# VIDEO.net
KiCad netlist of a schematic drawn in Altium Designer
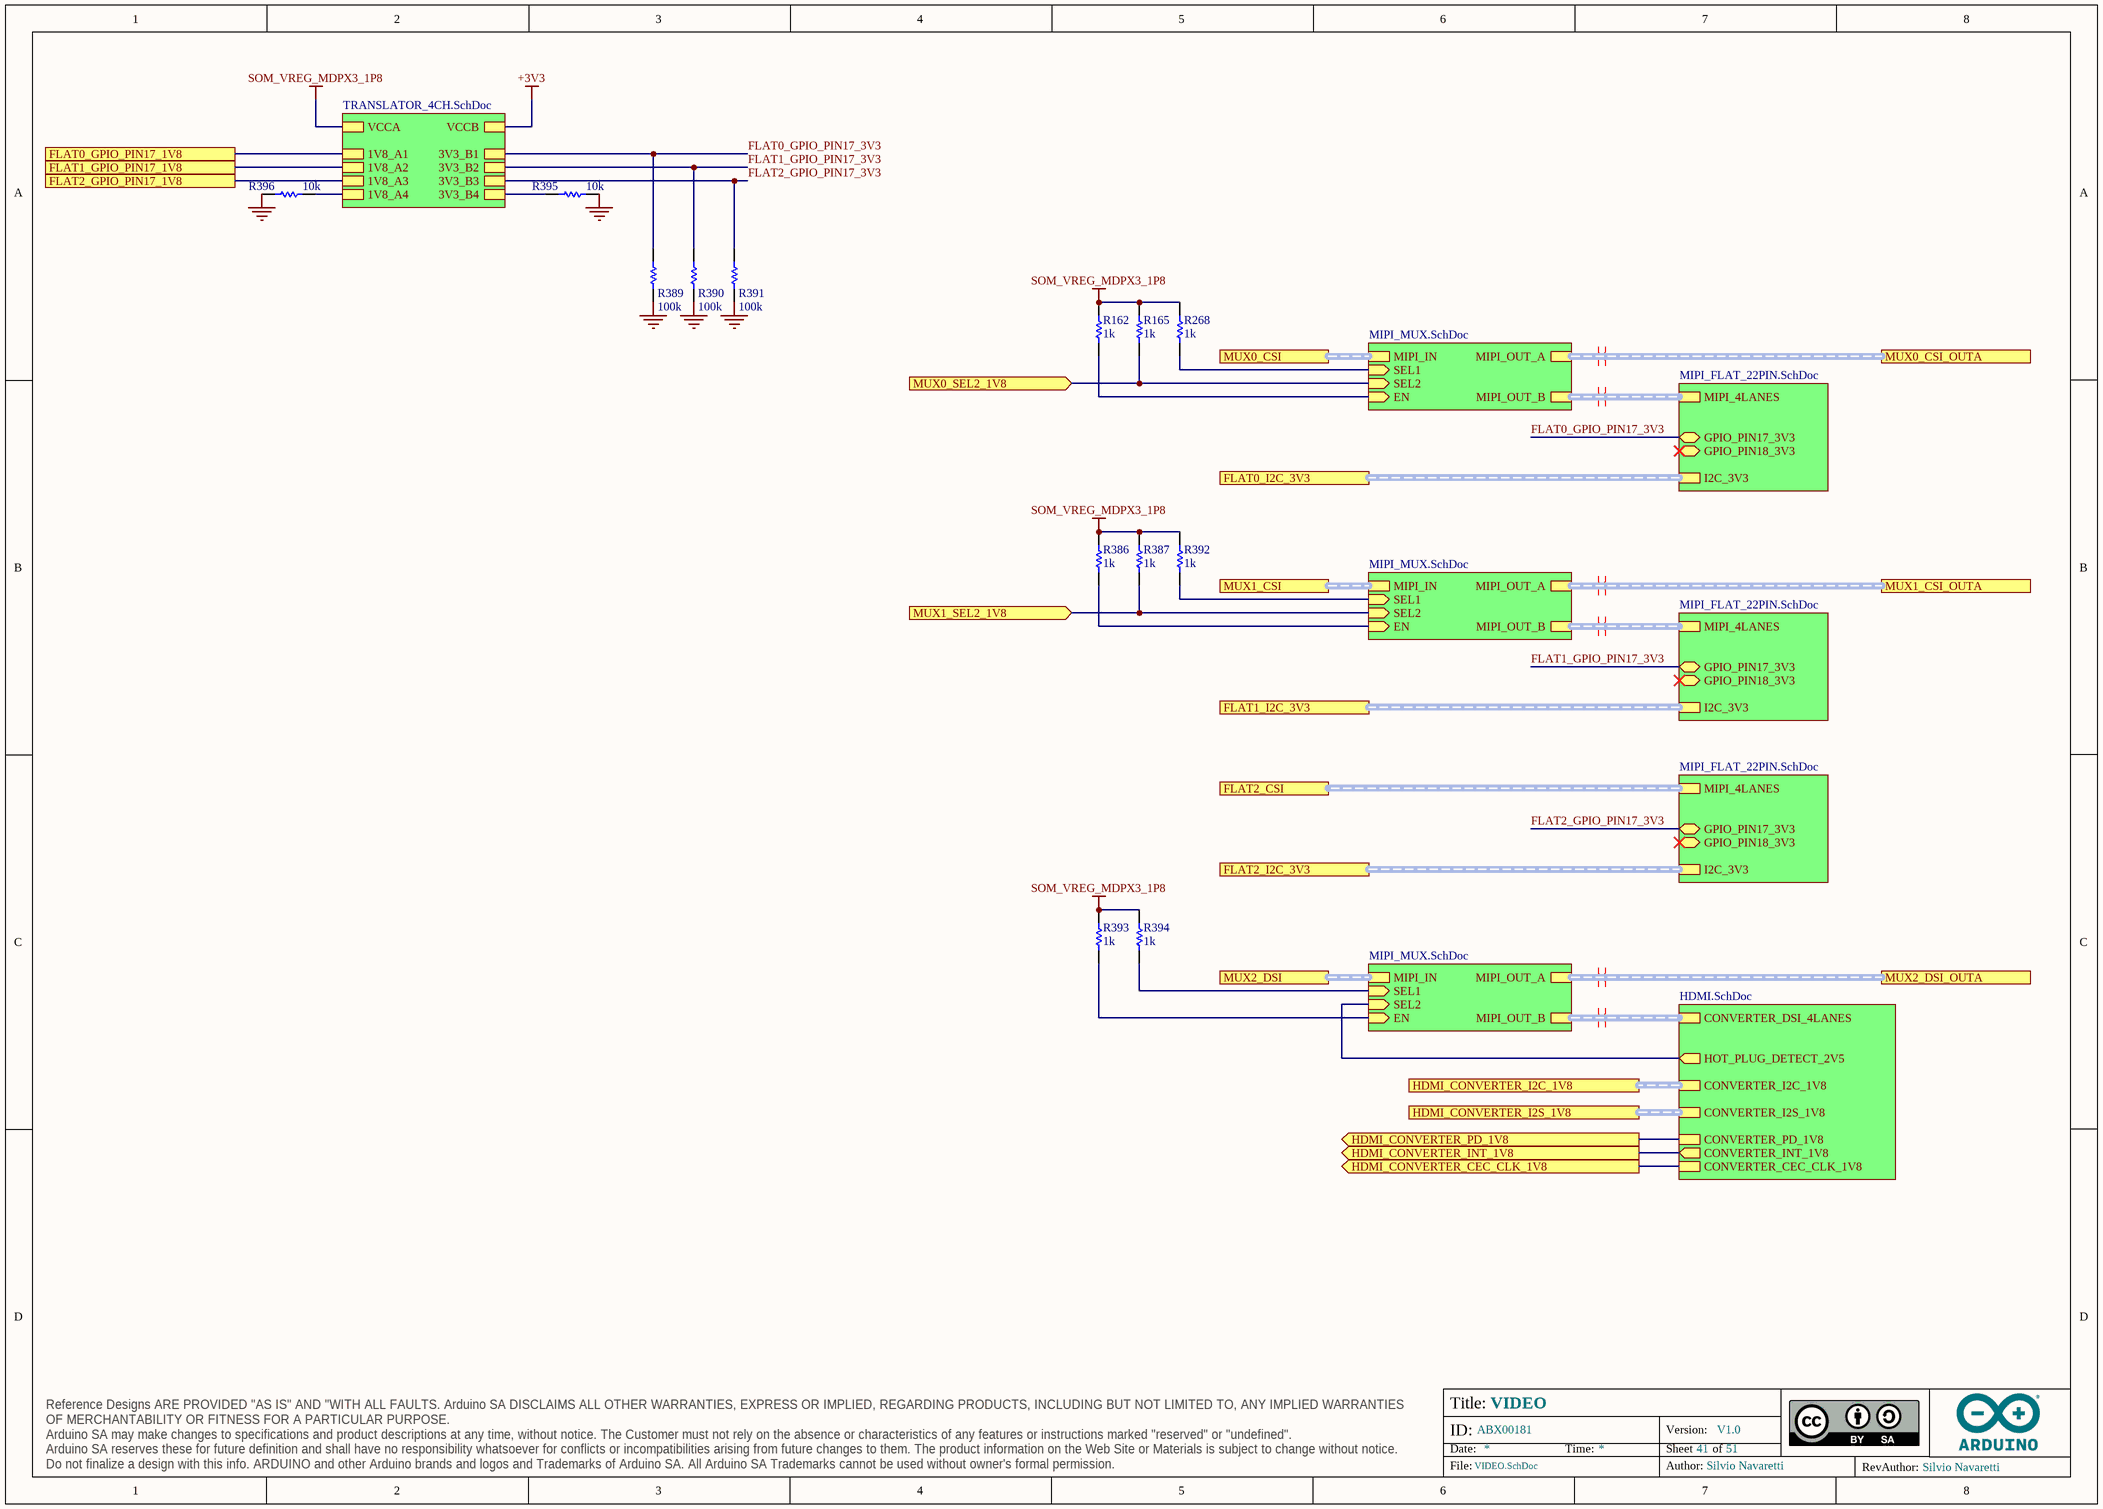
[diagram p0: VIDEO.SchDoc]

(export (version "E")
  (design (tool "Eeschema 10.0.6"))
  (components
    (comp (ref "R162")
      (value "1k")
      (footprint "RES-0201")
      (description "RES CHIP 0201 1k 1% 1/20W")
      (fields (field (name "POWER") "50mW") (field (name "TOLERANCE") "1%"))
      (libsource (lib "Clean") (part "RES"))
    )
    (comp (ref "R165")
      (value "1k")
      (footprint "RES-0201")
      (description "RES CHIP 0201 1k 1% 1/20W")
      (fields (field (name "POWER") "50mW") (field (name "TOLERANCE") "1%"))
      (libsource (lib "Clean") (part "RES"))
    )
    (comp (ref "R268")
      (value "1k")
      (footprint "RES-0201")
      (description "RES CHIP 0201 1k 1% 1/20W")
      (fields (field (name "POWER") "50mW") (field (name "TOLERANCE") "1%"))
      (libsource (lib "Clean") (part "RES"))
    )
    (comp (ref "R386")
      (value "1k")
      (footprint "RES-0201")
      (description "RES CHIP 0201 1k 1% 1/20W")
      (fields (field (name "POWER") "50mW") (field (name "TOLERANCE") "1%"))
      (libsource (lib "Clean") (part "RES"))
    )
    (comp (ref "R387")
      (value "1k")
      (footprint "RES-0201")
      (description "RES CHIP 0201 1k 1% 1/20W")
      (fields (field (name "POWER") "50mW") (field (name "TOLERANCE") "1%"))
      (libsource (lib "Clean") (part "RES"))
    )
    (comp (ref "R389")
      (value "100k")
      (footprint "RES-0201")
      (description "RES CHIP 0201 100k 1% 1/20W")
      (fields (field (name "POWER") "50mW") (field (name "TOLERANCE") "1%"))
      (libsource (lib "Clean") (part "RES"))
    )
    (comp (ref "R390")
      (value "100k")
      (footprint "RES-0201")
      (description "RES CHIP 0201 100k 1% 1/20W")
      (fields (field (name "POWER") "50mW") (field (name "TOLERANCE") "1%"))
      (libsource (lib "Clean") (part "RES"))
    )
    (comp (ref "R391")
      (value "100k")
      (footprint "RES-0201")
      (description "RES CHIP 0201 100k 1% 1/20W")
      (fields (field (name "POWER") "50mW") (field (name "TOLERANCE") "1%"))
      (libsource (lib "Clean") (part "RES"))
    )
    (comp (ref "R392")
      (value "1k")
      (footprint "RES-0201")
      (description "RES CHIP 0201 1k 1% 1/20W")
      (fields (field (name "POWER") "50mW") (field (name "TOLERANCE") "1%"))
      (libsource (lib "Clean") (part "RES"))
    )
    (comp (ref "R393")
      (value "1k")
      (footprint "RES-0201")
      (description "RES CHIP 0201 1k 1% 1/20W")
      (fields (field (name "POWER") "50mW") (field (name "TOLERANCE") "1%"))
      (libsource (lib "Clean") (part "RES"))
    )
    (comp (ref "R394")
      (value "1k")
      (footprint "RES-0201")
      (description "RES CHIP 0201 1k 1% 1/20W")
      (fields (field (name "POWER") "50mW") (field (name "TOLERANCE") "1%"))
      (libsource (lib "Clean") (part "RES"))
    )
    (comp (ref "R395")
      (value "10k")
      (footprint "RES-0201")
      (description "RES CHIP 0201 10k 1% 1/20W")
      (fields (field (name "POWER") "50mW") (field (name "TOLERANCE") "1%"))
      (libsource (lib "Clean") (part "RES"))
    )
    (comp (ref "R396")
      (value "10k")
      (footprint "RES-0201")
      (description "RES CHIP 0201 10k 1% 1/20W")
      (fields (field (name "POWER") "50mW") (field (name "TOLERANCE") "1%"))
      (libsource (lib "Clean") (part "RES"))
    )
  )
  (nets
    (net (code "4") (name "/1V8_A4") (class "Default")
      (node (ref "R396") (pin "2") (pinfunction "2_2") (pintype "passive"))
    )
    (net (code "5") (name "/3V3_B4") (class "Default")
      (node (ref "R395") (pin "1") (pinfunction "1_1") (pintype "passive"))
    )
    (net (code "7") (name "/EN") (class "Default")
      (node (ref "R386") (pin "2") (pinfunction "2_2") (pintype "passive"))
    )
    (net (code "8") (name "/EN_1") (class "Default")
      (node (ref "R162") (pin "2") (pinfunction "2_2") (pintype "passive"))
    )
    (net (code "9") (name "/EN_2") (class "Default")
      (node (ref "R393") (pin "1") (pinfunction "1_1") (pintype "passive"))
    )
    (net (code "11") (name "/FLAT0_GPIO_PIN17_3V3") (class "Default")
      (node (ref "R389") (pin "1") (pinfunction "1_1") (pintype "passive"))
    )
    (net (code "14") (name "/FLAT1_GPIO_PIN17_3V3") (class "Default")
      (node (ref "R390") (pin "1") (pinfunction "1_1") (pintype "passive"))
    )
    (net (code "18") (name "/FLAT2_GPIO_PIN17_3V3") (class "Default")
      (node (ref "R391") (pin "1") (pinfunction "1_1") (pintype "passive"))
    )
    (net (code "36") (name "/MUX0_SEL2_1V8") (class "Default")
      (node (ref "R165") (pin "1") (pinfunction "1_1") (pintype "passive"))
    )
    (net (code "39") (name "/MUX1_SEL2_1V8") (class "Default")
      (node (ref "R387") (pin "1") (pinfunction "1_1") (pintype "passive"))
    )
    (net (code "42") (name "/SEL1") (class "Default")
      (node (ref "R392") (pin "1") (pinfunction "1_1") (pintype "passive"))
    )
    (net (code "43") (name "/SEL1_1") (class "Default")
      (node (ref "R394") (pin "1") (pinfunction "1_1") (pintype "passive"))
    )
    (net (code "44") (name "/SEL1_2") (class "Default")
      (node (ref "R268") (pin "1") (pinfunction "1_1") (pintype "passive"))
    )
    (net (code "45") (name "GND") (class "Default")
      (node (ref "R389") (pin "2") (pinfunction "2_2") (pintype "passive"))
      (node (ref "R390") (pin "2") (pinfunction "2_2") (pintype "passive"))
      (node (ref "R391") (pin "2") (pinfunction "2_2") (pintype "passive"))
      (node (ref "R395") (pin "2") (pinfunction "2_2") (pintype "passive"))
      (node (ref "R396") (pin "1") (pinfunction "1_1") (pintype "passive"))
    )
    (net (code "46") (name "SOM_VREG_MDPX3_1P8") (class "Default")
      (node (ref "R162") (pin "1") (pinfunction "1_1") (pintype "passive"))
      (node (ref "R165") (pin "2") (pinfunction "2_2") (pintype "passive"))
      (node (ref "R268") (pin "2") (pinfunction "2_2") (pintype "passive"))
      (node (ref "R386") (pin "1") (pinfunction "1_1") (pintype "passive"))
      (node (ref "R387") (pin "2") (pinfunction "2_2") (pintype "passive"))
      (node (ref "R392") (pin "2") (pinfunction "2_2") (pintype "passive"))
      (node (ref "R393") (pin "2") (pinfunction "2_2") (pintype "passive"))
      (node (ref "R394") (pin "2") (pinfunction "2_2") (pintype "passive"))
    )
  )
)
